# power.net
KiCad netlist of a schematic drawn in Altium Designer
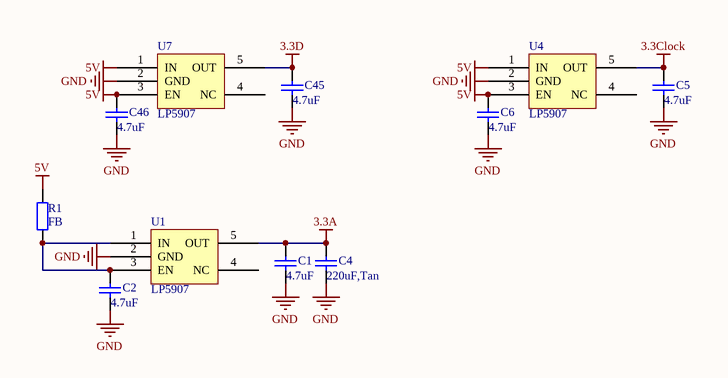
[diagram p0: power.SchDoc]

(export (version "E")
  (design (tool "Eeschema 10.0.6"))
  (components
    (comp (ref "C1")
      (value "4.7uF")
      (footprint "0603L")
      (description "Capacitor")
      (fields (field (name "PUBLISHER") "Altium Limited"))
      (libsource (lib "RTC6705") (part "Cap"))
    )
    (comp (ref "C2")
      (value "4.7uF")
      (footprint "0603L")
      (description "Capacitor")
      (fields (field (name "PUBLISHER") "Altium Limited"))
      (libsource (lib "RTC6705") (part "Cap"))
    )
    (comp (ref "C4")
      (value "220uF,Tan")
      (footprint "1210")
      (description "Capacitor")
      (fields (field (name "PUBLISHER") "Altium Limited"))
      (libsource (lib "RTC6705") (part "Cap"))
    )
    (comp (ref "C5")
      (value "4.7uF")
      (footprint "0603L")
      (description "Capacitor")
      (fields (field (name "PUBLISHER") "Altium Limited"))
      (libsource (lib "RTC6705") (part "Cap"))
    )
    (comp (ref "C6")
      (value "4.7uF")
      (footprint "0603L")
      (description "Capacitor")
      (fields (field (name "PUBLISHER") "Altium Limited"))
      (libsource (lib "RTC6705") (part "Cap"))
    )
    (comp (ref "C45")
      (value "4.7uF")
      (footprint "0603L")
      (description "Capacitor")
      (fields (field (name "PUBLISHER") "Altium Limited"))
      (libsource (lib "RTC6705") (part "Cap"))
    )
    (comp (ref "C46")
      (value "4.7uF")
      (footprint "0603L")
      (description "Capacitor")
      (fields (field (name "PUBLISHER") "Altium Limited"))
      (libsource (lib "RTC6705") (part "Cap"))
    )
    (comp (ref "R1")
      (value "FB")
      (footprint "0603L")
      (description "Resistor")
      (fields (field (name "PUBLISHER") "Altium Limited"))
      (libsource (lib "Miscellaneous Devices") (part "Res2"))
    )
    (comp (ref "U1") (value "LP5907") (footprint "SOT23-5") (libsource (lib "RTC6705") (part "LP5907")))
    (comp (ref "U4") (value "LP5907") (footprint "SOT23-5") (libsource (lib "RTC6705") (part "LP5907")))
    (comp (ref "U7") (value "LP5907") (footprint "SOT23-5") (libsource (lib "RTC6705") (part "LP5907")))
  )
  (nets
    (net (code "1") (name "3.3A") (class "Default")
      (node (ref "C1") (pin "2") (pinfunction "2_2") (pintype "passive"))
      (node (ref "C4") (pin "2") (pinfunction "2_2") (pintype "passive"))
      (node (ref "U1") (pin "5") (pinfunction "OUT_5") (pintype "passive"))
    )
    (net (code "2") (name "3.3Clock") (class "Default")
      (node (ref "C5") (pin "2") (pinfunction "2_2") (pintype "passive"))
      (node (ref "U4") (pin "5") (pinfunction "OUT_5") (pintype "passive"))
    )
    (net (code "3") (name "3.3D") (class "Default")
      (node (ref "C45") (pin "2") (pinfunction "2_2") (pintype "passive"))
      (node (ref "U7") (pin "5") (pinfunction "OUT_5") (pintype "passive"))
    )
    (net (code "4") (name "5V") (class "Default")
      (node (ref "C46") (pin "2") (pinfunction "2_2") (pintype "passive"))
      (node (ref "C6") (pin "2") (pinfunction "2_2") (pintype "passive"))
      (node (ref "R1") (pin "2") (pinfunction "2_2") (pintype "passive"))
      (node (ref "U4") (pin "1") (pinfunction "IN_1") (pintype "passive"))
      (node (ref "U4") (pin "3") (pinfunction "EN_3") (pintype "passive"))
      (node (ref "U7") (pin "1") (pinfunction "IN_1") (pintype "passive"))
      (node (ref "U7") (pin "3") (pinfunction "EN_3") (pintype "passive"))
    )
    (net (code "5") (name "GND") (class "Default")
      (node (ref "C1") (pin "1") (pinfunction "1_1") (pintype "passive"))
      (node (ref "C2") (pin "1") (pinfunction "1_1") (pintype "passive"))
      (node (ref "C4") (pin "1") (pinfunction "1_1") (pintype "passive"))
      (node (ref "C45") (pin "1") (pinfunction "1_1") (pintype "passive"))
      (node (ref "C46") (pin "1") (pinfunction "1_1") (pintype "passive"))
      (node (ref "C5") (pin "1") (pinfunction "1_1") (pintype "passive"))
      (node (ref "C6") (pin "1") (pinfunction "1_1") (pintype "passive"))
      (node (ref "U1") (pin "2") (pinfunction "GND_2") (pintype "passive"))
      (node (ref "U4") (pin "2") (pinfunction "GND_2") (pintype "passive"))
      (node (ref "U7") (pin "2") (pinfunction "GND_2") (pintype "passive"))
    )
    (net (code "6") (name "Net-(U1-EN)") (class "Default")
      (node (ref "C2") (pin "2") (pinfunction "2_2") (pintype "passive"))
      (node (ref "R1") (pin "1") (pinfunction "1_1") (pintype "passive"))
      (node (ref "U1") (pin "1") (pinfunction "IN_1") (pintype "passive"))
      (node (ref "U1") (pin "3") (pinfunction "EN_3") (pintype "passive"))
    )
    (net (code "7") (name "unconnected-(U1-NC-Pad4)") (class "Default")
      (node (ref "U1") (pin "4") (pinfunction "NC_4") (pintype "passive"))
    )
    (net (code "8") (name "unconnected-(U4-NC-Pad4)") (class "Default")
      (node (ref "U4") (pin "4") (pinfunction "NC_4") (pintype "passive"))
    )
    (net (code "9") (name "unconnected-(U7-NC-Pad4)") (class "Default")
      (node (ref "U7") (pin "4") (pinfunction "NC_4") (pintype "passive"))
    )
  )
)
